# design.net
KiCad netlist of a schematic drawn in Altium Designer
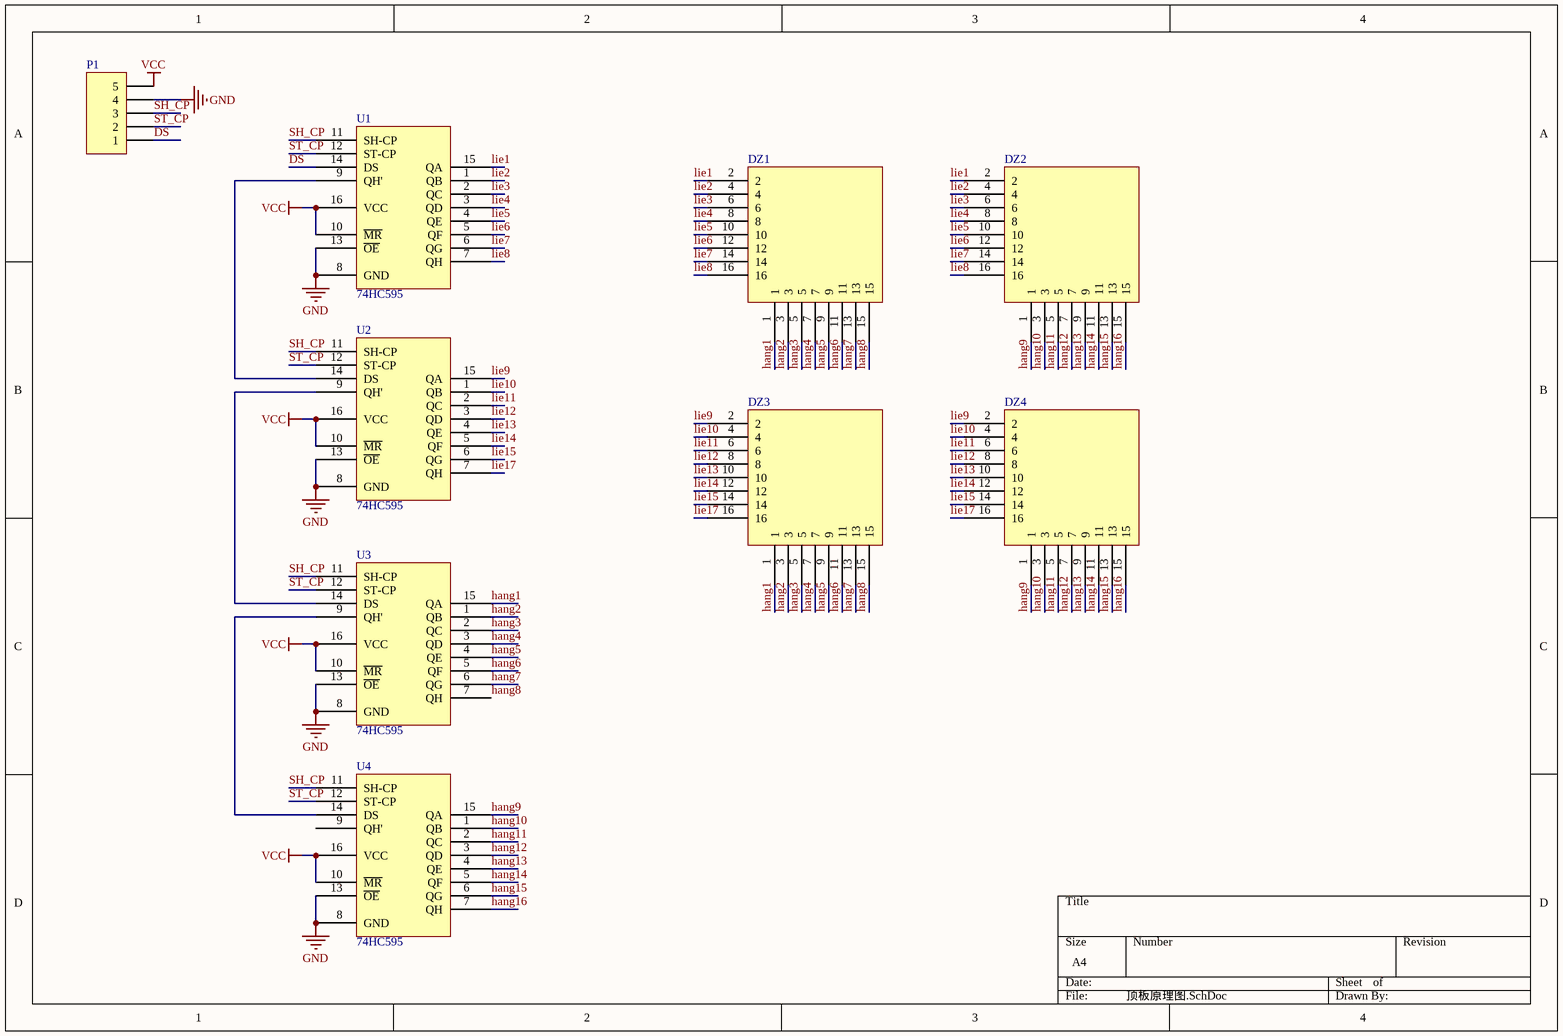
[diagram p0: 顶板原理图.SchDoc]

(export (version "E")
  (design (tool "Eeschema 10.0.6"))
  (components
    (comp (ref "DZ1")
      (value "DianZhen")
      (footprint "DianZhen")
      (libsource (lib "MY_SCH_LIB") (part "DianZhen"))
    )
    (comp (ref "DZ2")
      (value "DianZhen")
      (footprint "DianZhen")
      (libsource (lib "MY_SCH_LIB") (part "DianZhen"))
    )
    (comp (ref "DZ3")
      (value "DianZhen")
      (footprint "DianZhen")
      (libsource (lib "MY_SCH_LIB") (part "DianZhen"))
    )
    (comp (ref "DZ4")
      (value "DianZhen")
      (footprint "DianZhen")
      (libsource (lib "MY_SCH_LIB") (part "DianZhen"))
    )
    (comp (ref "P1")
      (value "Header 5")
      (footprint "HDR1X5")
      (description "Header, 5-Pin")
      (fields (field (name "PUBLISHER") "Altium Limited"))
      (libsource (lib "Miscellaneous Connectors") (part "Header 5"))
    )
    (comp (ref "U1") (value "74HC595") (footprint "SOIC16_L") (libsource (lib "MY_SCH_LIB") (part "74HC595")))
    (comp (ref "U2") (value "74HC595") (footprint "SOIC16_L") (libsource (lib "MY_SCH_LIB") (part "74HC595")))
    (comp (ref "U3") (value "74HC595") (footprint "SOIC16_L") (libsource (lib "MY_SCH_LIB") (part "74HC595")))
    (comp (ref "U4") (value "74HC595") (footprint "SOIC16_L") (libsource (lib "MY_SCH_LIB") (part "74HC595")))
  )
  (nets
    (net (code "1") (name "/DS") (class "Default")
      (node (ref "P1") (pin "1") (pinfunction "1_1") (pintype "passive"))
      (node (ref "U1") (pin "14") (pinfunction "DS_14") (pintype "passive"))
    )
    (net (code "2") (name "/SH_CP") (class "Default")
      (node (ref "P1") (pin "3") (pinfunction "3_3") (pintype "passive"))
      (node (ref "U1") (pin "11") (pinfunction "SH-CP_11") (pintype "passive"))
      (node (ref "U2") (pin "11") (pinfunction "SH-CP_11") (pintype "passive"))
      (node (ref "U3") (pin "11") (pinfunction "SH-CP_11") (pintype "passive"))
      (node (ref "U4") (pin "11") (pinfunction "SH-CP_11") (pintype "passive"))
    )
    (net (code "3") (name "/ST_CP") (class "Default")
      (node (ref "P1") (pin "2") (pinfunction "2_2") (pintype "passive"))
      (node (ref "U1") (pin "12") (pinfunction "ST-CP_12") (pintype "passive"))
      (node (ref "U2") (pin "12") (pinfunction "ST-CP_12") (pintype "passive"))
      (node (ref "U3") (pin "12") (pinfunction "ST-CP_12") (pintype "passive"))
      (node (ref "U4") (pin "12") (pinfunction "ST-CP_12") (pintype "passive"))
    )
    (net (code "4") (name "/hang1") (class "Default")
      (node (ref "DZ1") (pin "1") (pinfunction "1_1") (pintype "passive"))
      (node (ref "DZ3") (pin "1") (pinfunction "1_1") (pintype "passive"))
      (node (ref "U3") (pin "15") (pinfunction "QA_15") (pintype "passive"))
    )
    (net (code "5") (name "/hang2") (class "Default")
      (node (ref "DZ1") (pin "3") (pinfunction "3_3") (pintype "passive"))
      (node (ref "DZ3") (pin "3") (pinfunction "3_3") (pintype "passive"))
      (node (ref "U3") (pin "1") (pinfunction "QB_1") (pintype "passive"))
    )
    (net (code "6") (name "/hang3") (class "Default")
      (node (ref "DZ1") (pin "5") (pinfunction "5_5") (pintype "passive"))
      (node (ref "DZ3") (pin "5") (pinfunction "5_5") (pintype "passive"))
      (node (ref "U3") (pin "2") (pinfunction "QC_2") (pintype "passive"))
    )
    (net (code "7") (name "/hang4") (class "Default")
      (node (ref "DZ1") (pin "7") (pinfunction "7_7") (pintype "passive"))
      (node (ref "DZ3") (pin "7") (pinfunction "7_7") (pintype "passive"))
      (node (ref "U3") (pin "3") (pinfunction "QD_3") (pintype "passive"))
    )
    (net (code "8") (name "/hang5") (class "Default")
      (node (ref "DZ1") (pin "9") (pinfunction "9_9") (pintype "passive"))
      (node (ref "DZ3") (pin "9") (pinfunction "9_9") (pintype "passive"))
      (node (ref "U3") (pin "4") (pinfunction "QE_4") (pintype "passive"))
    )
    (net (code "9") (name "/hang6") (class "Default")
      (node (ref "DZ1") (pin "11") (pinfunction "11_11") (pintype "passive"))
      (node (ref "DZ3") (pin "11") (pinfunction "11_11") (pintype "passive"))
      (node (ref "U3") (pin "5") (pinfunction "QF_5") (pintype "passive"))
    )
    (net (code "10") (name "/hang7") (class "Default")
      (node (ref "DZ1") (pin "13") (pinfunction "13_13") (pintype "passive"))
      (node (ref "DZ3") (pin "13") (pinfunction "13_13") (pintype "passive"))
      (node (ref "U3") (pin "6") (pinfunction "QG_6") (pintype "passive"))
    )
    (net (code "11") (name "/hang8") (class "Default")
      (node (ref "DZ1") (pin "15") (pinfunction "15_15") (pintype "passive"))
      (node (ref "DZ3") (pin "15") (pinfunction "15_15") (pintype "passive"))
      (node (ref "U3") (pin "7") (pinfunction "QH_7") (pintype "passive"))
    )
    (net (code "12") (name "/hang9") (class "Default")
      (node (ref "DZ2") (pin "1") (pinfunction "1_1") (pintype "passive"))
      (node (ref "DZ4") (pin "1") (pinfunction "1_1") (pintype "passive"))
      (node (ref "U4") (pin "15") (pinfunction "QA_15") (pintype "passive"))
    )
    (net (code "13") (name "/hang10") (class "Default")
      (node (ref "DZ2") (pin "3") (pinfunction "3_3") (pintype "passive"))
      (node (ref "DZ4") (pin "3") (pinfunction "3_3") (pintype "passive"))
      (node (ref "U4") (pin "1") (pinfunction "QB_1") (pintype "passive"))
    )
    (net (code "14") (name "/hang11") (class "Default")
      (node (ref "DZ2") (pin "5") (pinfunction "5_5") (pintype "passive"))
      (node (ref "DZ4") (pin "5") (pinfunction "5_5") (pintype "passive"))
      (node (ref "U4") (pin "2") (pinfunction "QC_2") (pintype "passive"))
    )
    (net (code "15") (name "/hang12") (class "Default")
      (node (ref "DZ2") (pin "7") (pinfunction "7_7") (pintype "passive"))
      (node (ref "DZ4") (pin "7") (pinfunction "7_7") (pintype "passive"))
      (node (ref "U4") (pin "3") (pinfunction "QD_3") (pintype "passive"))
    )
    (net (code "16") (name "/hang13") (class "Default")
      (node (ref "DZ2") (pin "9") (pinfunction "9_9") (pintype "passive"))
      (node (ref "DZ4") (pin "9") (pinfunction "9_9") (pintype "passive"))
      (node (ref "U4") (pin "4") (pinfunction "QE_4") (pintype "passive"))
    )
    (net (code "17") (name "/hang14") (class "Default")
      (node (ref "DZ2") (pin "11") (pinfunction "11_11") (pintype "passive"))
      (node (ref "DZ4") (pin "11") (pinfunction "11_11") (pintype "passive"))
      (node (ref "U4") (pin "5") (pinfunction "QF_5") (pintype "passive"))
    )
    (net (code "18") (name "/hang15") (class "Default")
      (node (ref "DZ2") (pin "13") (pinfunction "13_13") (pintype "passive"))
      (node (ref "DZ4") (pin "13") (pinfunction "13_13") (pintype "passive"))
      (node (ref "U4") (pin "6") (pinfunction "QG_6") (pintype "passive"))
    )
    (net (code "19") (name "/hang16") (class "Default")
      (node (ref "DZ2") (pin "15") (pinfunction "15_15") (pintype "passive"))
      (node (ref "DZ4") (pin "15") (pinfunction "15_15") (pintype "passive"))
      (node (ref "U4") (pin "7") (pinfunction "QH_7") (pintype "passive"))
    )
    (net (code "20") (name "/lie1") (class "Default")
      (node (ref "DZ1") (pin "2") (pinfunction "2_2") (pintype "passive"))
      (node (ref "DZ2") (pin "2") (pinfunction "2_2") (pintype "passive"))
      (node (ref "U1") (pin "15") (pinfunction "QA_15") (pintype "passive"))
    )
    (net (code "21") (name "/lie2") (class "Default")
      (node (ref "DZ1") (pin "4") (pinfunction "4_4") (pintype "passive"))
      (node (ref "DZ2") (pin "4") (pinfunction "4_4") (pintype "passive"))
      (node (ref "U1") (pin "1") (pinfunction "QB_1") (pintype "passive"))
    )
    (net (code "22") (name "/lie3") (class "Default")
      (node (ref "DZ1") (pin "6") (pinfunction "6_6") (pintype "passive"))
      (node (ref "DZ2") (pin "6") (pinfunction "6_6") (pintype "passive"))
      (node (ref "U1") (pin "2") (pinfunction "QC_2") (pintype "passive"))
    )
    (net (code "23") (name "/lie4") (class "Default")
      (node (ref "DZ1") (pin "8") (pinfunction "8_8") (pintype "passive"))
      (node (ref "DZ2") (pin "8") (pinfunction "8_8") (pintype "passive"))
      (node (ref "U1") (pin "3") (pinfunction "QD_3") (pintype "passive"))
    )
    (net (code "24") (name "/lie5") (class "Default")
      (node (ref "DZ1") (pin "10") (pinfunction "10_10") (pintype "passive"))
      (node (ref "DZ2") (pin "10") (pinfunction "10_10") (pintype "passive"))
      (node (ref "U1") (pin "4") (pinfunction "QE_4") (pintype "passive"))
    )
    (net (code "25") (name "/lie6") (class "Default")
      (node (ref "DZ1") (pin "12") (pinfunction "12_12") (pintype "passive"))
      (node (ref "DZ2") (pin "12") (pinfunction "12_12") (pintype "passive"))
      (node (ref "U1") (pin "5") (pinfunction "QF_5") (pintype "passive"))
    )
    (net (code "26") (name "/lie7") (class "Default")
      (node (ref "DZ1") (pin "14") (pinfunction "14_14") (pintype "passive"))
      (node (ref "DZ2") (pin "14") (pinfunction "14_14") (pintype "passive"))
      (node (ref "U1") (pin "6") (pinfunction "QG_6") (pintype "passive"))
    )
    (net (code "27") (name "/lie8") (class "Default")
      (node (ref "DZ1") (pin "16") (pinfunction "16_16") (pintype "passive"))
      (node (ref "DZ2") (pin "16") (pinfunction "16_16") (pintype "passive"))
      (node (ref "U1") (pin "7") (pinfunction "QH_7") (pintype "passive"))
    )
    (net (code "28") (name "/lie9") (class "Default")
      (node (ref "DZ3") (pin "2") (pinfunction "2_2") (pintype "passive"))
      (node (ref "DZ4") (pin "2") (pinfunction "2_2") (pintype "passive"))
      (node (ref "U2") (pin "15") (pinfunction "QA_15") (pintype "passive"))
    )
    (net (code "29") (name "/lie10") (class "Default")
      (node (ref "DZ3") (pin "4") (pinfunction "4_4") (pintype "passive"))
      (node (ref "DZ4") (pin "4") (pinfunction "4_4") (pintype "passive"))
      (node (ref "U2") (pin "1") (pinfunction "QB_1") (pintype "passive"))
    )
    (net (code "30") (name "/lie11") (class "Default")
      (node (ref "DZ3") (pin "6") (pinfunction "6_6") (pintype "passive"))
      (node (ref "DZ4") (pin "6") (pinfunction "6_6") (pintype "passive"))
      (node (ref "U2") (pin "2") (pinfunction "QC_2") (pintype "passive"))
    )
    (net (code "31") (name "/lie12") (class "Default")
      (node (ref "DZ3") (pin "8") (pinfunction "8_8") (pintype "passive"))
      (node (ref "DZ4") (pin "8") (pinfunction "8_8") (pintype "passive"))
      (node (ref "U2") (pin "3") (pinfunction "QD_3") (pintype "passive"))
    )
    (net (code "32") (name "/lie13") (class "Default")
      (node (ref "DZ3") (pin "10") (pinfunction "10_10") (pintype "passive"))
      (node (ref "DZ4") (pin "10") (pinfunction "10_10") (pintype "passive"))
      (node (ref "U2") (pin "4") (pinfunction "QE_4") (pintype "passive"))
    )
    (net (code "33") (name "/lie14") (class "Default")
      (node (ref "DZ3") (pin "12") (pinfunction "12_12") (pintype "passive"))
      (node (ref "DZ4") (pin "12") (pinfunction "12_12") (pintype "passive"))
      (node (ref "U2") (pin "5") (pinfunction "QF_5") (pintype "passive"))
    )
    (net (code "34") (name "/lie15") (class "Default")
      (node (ref "DZ3") (pin "14") (pinfunction "14_14") (pintype "passive"))
      (node (ref "DZ4") (pin "14") (pinfunction "14_14") (pintype "passive"))
      (node (ref "U2") (pin "6") (pinfunction "QG_6") (pintype "passive"))
    )
    (net (code "35") (name "/lie17") (class "Default")
      (node (ref "DZ3") (pin "16") (pinfunction "16_16") (pintype "passive"))
      (node (ref "DZ4") (pin "16") (pinfunction "16_16") (pintype "passive"))
      (node (ref "U2") (pin "7") (pinfunction "QH_7") (pintype "passive"))
    )
    (net (code "36") (name "GND") (class "Default")
      (node (ref "P1") (pin "4") (pinfunction "4_4") (pintype "passive"))
      (node (ref "U1") (pin "13") (pinfunction "~{OE}_13") (pintype "passive"))
      (node (ref "U1") (pin "8") (pinfunction "GND_8") (pintype "passive"))
      (node (ref "U2") (pin "13") (pinfunction "~{OE}_13") (pintype "passive"))
      (node (ref "U2") (pin "8") (pinfunction "GND_8") (pintype "passive"))
      (node (ref "U3") (pin "13") (pinfunction "~{OE}_13") (pintype "passive"))
      (node (ref "U3") (pin "8") (pinfunction "GND_8") (pintype "passive"))
      (node (ref "U4") (pin "13") (pinfunction "~{OE}_13") (pintype "passive"))
      (node (ref "U4") (pin "8") (pinfunction "GND_8") (pintype "passive"))
    )
    (net (code "37") (name "Net-(U1-QH')") (class "Default")
      (node (ref "U1") (pin "9") (pinfunction "QH'_9") (pintype "passive"))
      (node (ref "U2") (pin "14") (pinfunction "DS_14") (pintype "passive"))
    )
    (net (code "38") (name "Net-(U2-QH')") (class "Default")
      (node (ref "U2") (pin "9") (pinfunction "QH'_9") (pintype "passive"))
      (node (ref "U3") (pin "14") (pinfunction "DS_14") (pintype "passive"))
    )
    (net (code "39") (name "Net-(U3-QH')") (class "Default")
      (node (ref "U3") (pin "9") (pinfunction "QH'_9") (pintype "passive"))
      (node (ref "U4") (pin "14") (pinfunction "DS_14") (pintype "passive"))
    )
    (net (code "40") (name "VCC") (class "Default")
      (node (ref "P1") (pin "5") (pinfunction "5_5") (pintype "passive"))
      (node (ref "U1") (pin "10") (pinfunction "~{MR}_10") (pintype "passive"))
      (node (ref "U1") (pin "16") (pinfunction "VCC_16") (pintype "passive"))
      (node (ref "U2") (pin "10") (pinfunction "~{MR}_10") (pintype "passive"))
      (node (ref "U2") (pin "16") (pinfunction "VCC_16") (pintype "passive"))
      (node (ref "U3") (pin "10") (pinfunction "~{MR}_10") (pintype "passive"))
      (node (ref "U3") (pin "16") (pinfunction "VCC_16") (pintype "passive"))
      (node (ref "U4") (pin "10") (pinfunction "~{MR}_10") (pintype "passive"))
      (node (ref "U4") (pin "16") (pinfunction "VCC_16") (pintype "passive"))
    )
    (net (code "41") (name "unconnected-(U4-QH'-Pad9)") (class "Default")
      (node (ref "U4") (pin "9") (pinfunction "QH'_9") (pintype "passive"))
    )
  )
)
